# platine.net
KiCad netlist of a schematic drawn in EAGLE
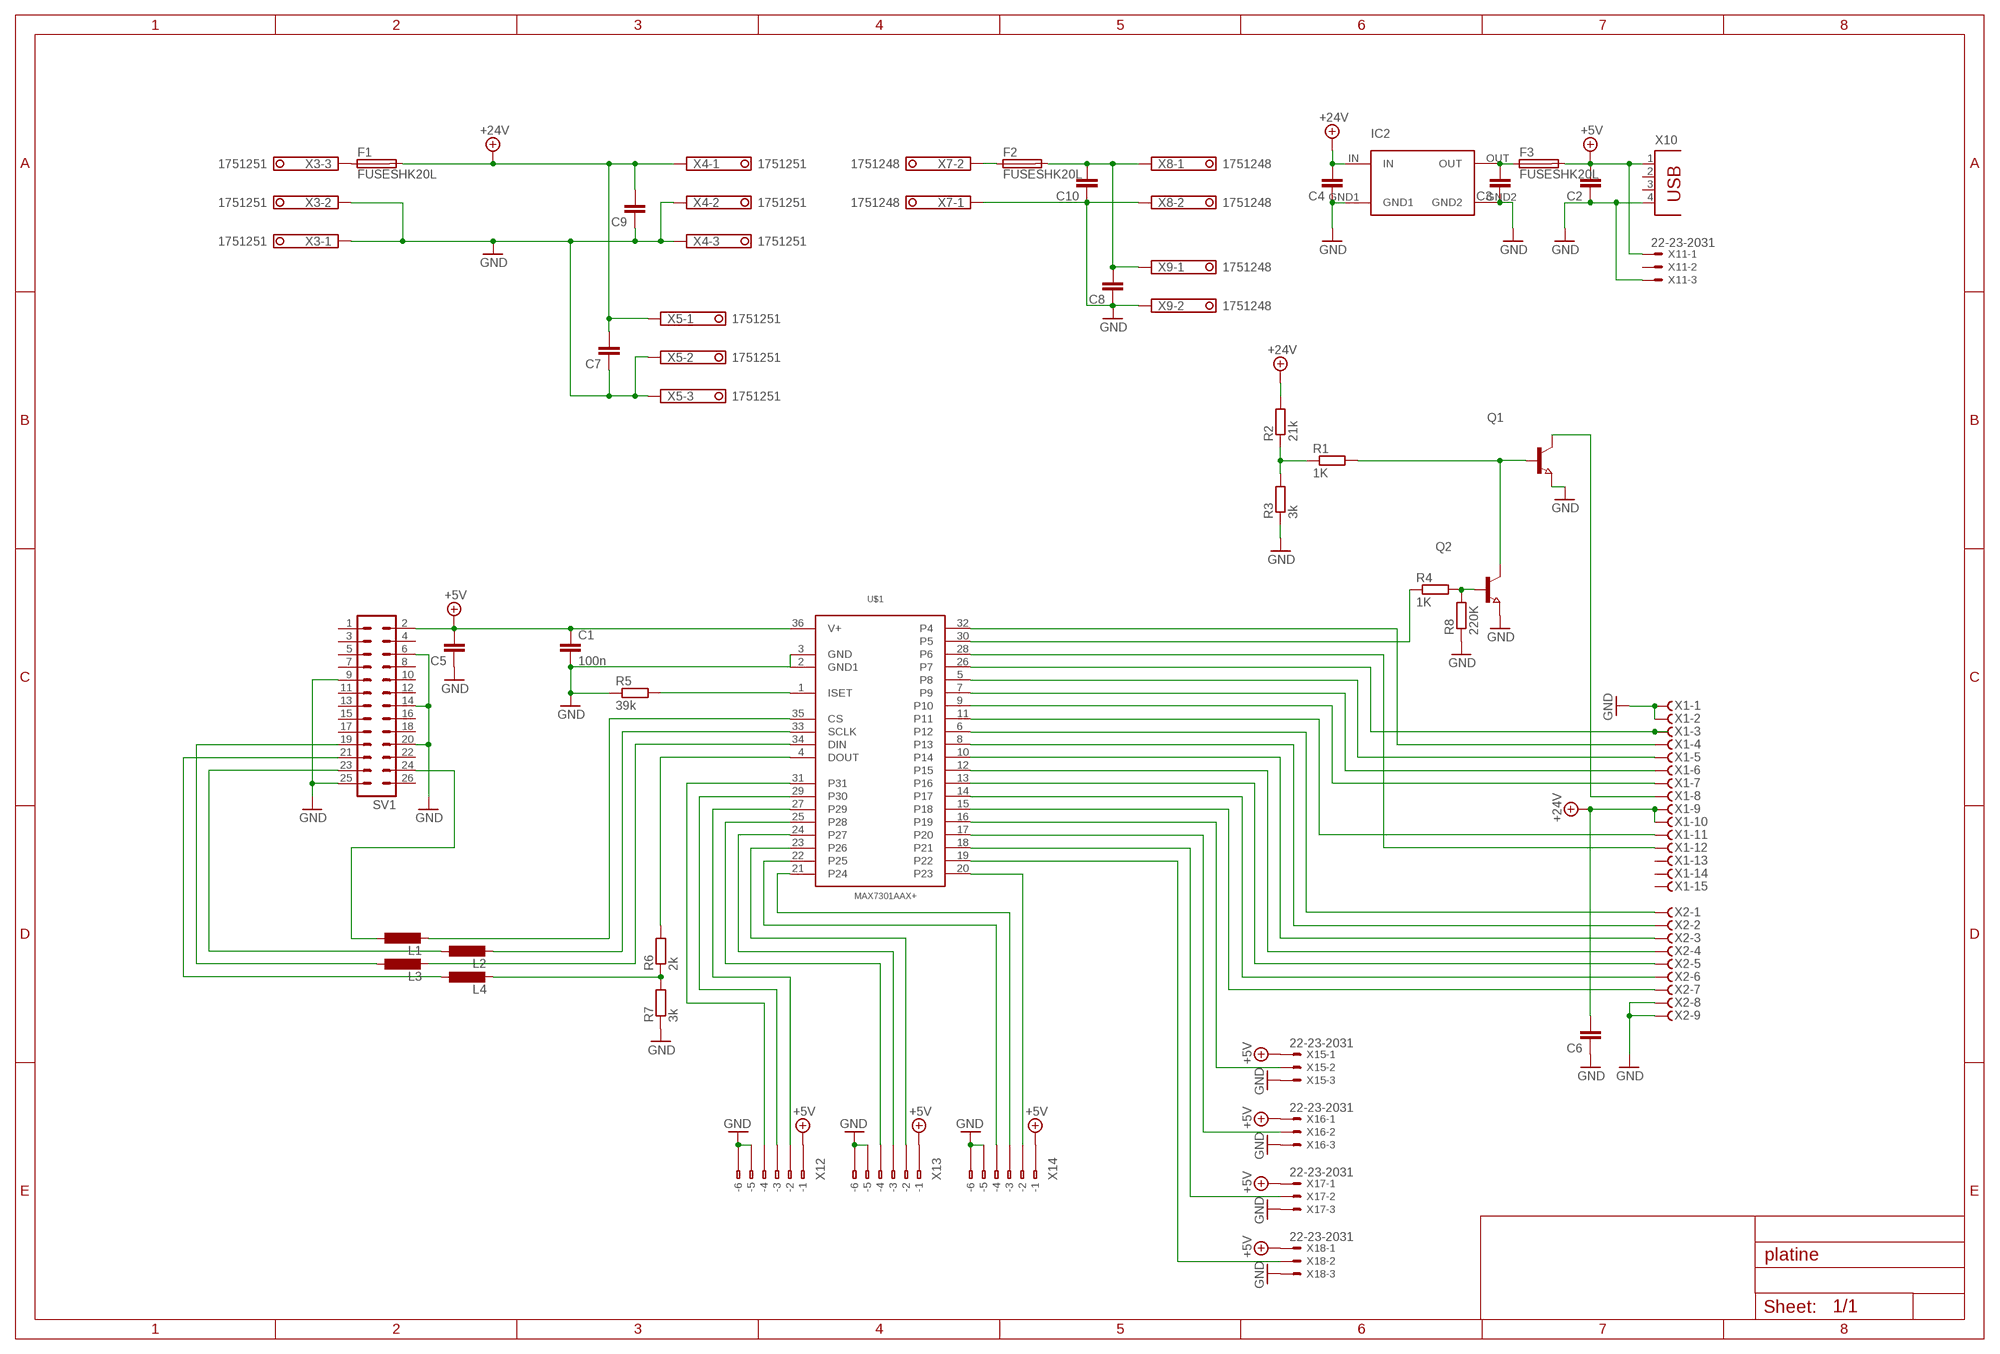
[diagram p0: schematic, sheet 1]

(export (version "E")
  (design (tool "Eeschema 10.0.6"))
  (components
    (comp (ref "C1")
      (value "100n")
      (footprint "eagle-import:C0603")
      (libsource (lib "eagle-import") (part "C-EUC0603"))
    )
    (comp (ref "C2")
      (value "C-EUC1206")
      (footprint "eagle-import:C1206")
      (libsource (lib "eagle-import") (part "C-EUC1206"))
    )
    (comp (ref "C3")
      (value "C-EUC1206")
      (footprint "eagle-import:C1206")
      (libsource (lib "eagle-import") (part "C-EUC1206"))
    )
    (comp (ref "C4")
      (value "C-EUC1206")
      (footprint "eagle-import:C1206")
      (libsource (lib "eagle-import") (part "C-EUC1206"))
    )
    (comp (ref "C5")
      (value "C-EUC1206")
      (footprint "eagle-import:C1206")
      (libsource (lib "eagle-import") (part "C-EUC1206"))
    )
    (comp (ref "C6")
      (value "C-EUC1206")
      (footprint "eagle-import:C1206")
      (libsource (lib "eagle-import") (part "C-EUC1206"))
    )
    (comp (ref "C7")
      (value "C-EUC1206")
      (footprint "eagle-import:C1206")
      (libsource (lib "eagle-import") (part "C-EUC1206"))
    )
    (comp (ref "C8")
      (value "C-EUC1206")
      (footprint "eagle-import:C1206")
      (libsource (lib "eagle-import") (part "C-EUC1206"))
    )
    (comp (ref "C9")
      (value "C-EUC1206")
      (footprint "eagle-import:C1206")
      (libsource (lib "eagle-import") (part "C-EUC1206"))
    )
    (comp (ref "C10")
      (value "C-EUC1206")
      (footprint "eagle-import:C1206")
      (libsource (lib "eagle-import") (part "C-EUC1206"))
    )
    (comp (ref "F1")
      (value "FUSESHK20L")
      (footprint "eagle-import:SHK20L")
      (libsource (lib "eagle-import") (part "FUSESHK20L"))
    )
    (comp (ref "F2")
      (value "FUSESHK20L")
      (footprint "eagle-import:SHK20L")
      (libsource (lib "eagle-import") (part "FUSESHK20L"))
    )
    (comp (ref "F3")
      (value "FUSESHK20L")
      (footprint "eagle-import:SHK20L")
      (libsource (lib "eagle-import") (part "FUSESHK20L"))
    )
    (comp (ref "IC2")
      (value "SPS-1")
      (footprint "eagle-import:SPS-1")
      (libsource (lib "eagle-import") (part "SPS-1"))
    )
    (comp (ref "L1")
      (value "L-EUL0402")
      (footprint "eagle-import:R0402")
      (libsource (lib "eagle-import") (part "L-EUL0402"))
    )
    (comp (ref "L2")
      (value "L-EUL0402")
      (footprint "eagle-import:R0402")
      (libsource (lib "eagle-import") (part "L-EUL0402"))
    )
    (comp (ref "L3")
      (value "L-EUL0402")
      (footprint "eagle-import:R0402")
      (libsource (lib "eagle-import") (part "L-EUL0402"))
    )
    (comp (ref "L4")
      (value "L-EUL0402")
      (footprint "eagle-import:R0402")
      (libsource (lib "eagle-import") (part "L-EUL0402"))
    )
    (comp (ref "Q1")
      (value "NPN-TRANSISTOR_SOT23")
      (footprint "eagle-import:SOT23")
      (libsource (lib "eagle-import") (part "NPN-TRANSISTOR_SOT23"))
    )
    (comp (ref "Q2")
      (value "NPN-TRANSISTOR_SOT23")
      (footprint "eagle-import:SOT23")
      (libsource (lib "eagle-import") (part "NPN-TRANSISTOR_SOT23"))
    )
    (comp (ref "R1")
      (value "1K")
      (footprint "eagle-import:R0603")
      (libsource (lib "eagle-import") (part "R-EU_R0603"))
    )
    (comp (ref "R2")
      (value "21k")
      (footprint "eagle-import:R0603")
      (libsource (lib "eagle-import") (part "R-EU_R0603"))
    )
    (comp (ref "R3")
      (value "3k")
      (footprint "eagle-import:R0603")
      (libsource (lib "eagle-import") (part "R-EU_R0603"))
    )
    (comp (ref "R4")
      (value "1K")
      (footprint "eagle-import:R0603")
      (libsource (lib "eagle-import") (part "R-EU_R0603"))
    )
    (comp (ref "R5")
      (value "39k")
      (footprint "eagle-import:R0603")
      (libsource (lib "eagle-import") (part "R-EU_R0603"))
    )
    (comp (ref "R6")
      (value "2k")
      (footprint "eagle-import:R0603")
      (libsource (lib "eagle-import") (part "R-EU_R0603"))
    )
    (comp (ref "R7")
      (value "3k")
      (footprint "eagle-import:R0603")
      (libsource (lib "eagle-import") (part "R-EU_R0603"))
    )
    (comp (ref "R8")
      (value "220K")
      (footprint "eagle-import:R0603")
      (libsource (lib "eagle-import") (part "R-EU_R0603"))
    )
    (comp (ref "SV1")
      (value "MA13-2")
      (footprint "eagle-import:MA13-2")
      (libsource (lib "eagle-import") (part "MA13-2"))
    )
    (comp (ref "U$1")
      (value "MAX7301AAX+")
      (footprint "eagle-import:SSOP36")
      (libsource (lib "eagle-import") (part "MAX7301AAX+"))
    )
    (comp (ref "X1")
      (value "F15HPS")
      (footprint "eagle-import:F15HP")
      (libsource (lib "eagle-import") (part "F15?SHP"))
    )
    (comp (ref "X2")
      (value "F09HPS")
      (footprint "eagle-import:F09HP")
      (libsource (lib "eagle-import") (part "F09?SHP"))
    )
    (comp (ref "X3")
      (value "1751251")
      (footprint "eagle-import:1751251")
      (libsource (lib "eagle-import") (part "1751251"))
    )
    (comp (ref "X4")
      (value "1751251")
      (footprint "eagle-import:1751251")
      (libsource (lib "eagle-import") (part "1751251"))
    )
    (comp (ref "X5")
      (value "1751251")
      (footprint "eagle-import:1751251")
      (libsource (lib "eagle-import") (part "1751251"))
    )
    (comp (ref "X7")
      (value "1751248")
      (footprint "eagle-import:1751248")
      (libsource (lib "eagle-import") (part "1751248"))
    )
    (comp (ref "X8")
      (value "1751248")
      (footprint "eagle-import:1751248")
      (libsource (lib "eagle-import") (part "1751248"))
    )
    (comp (ref "X9")
      (value "1751248")
      (footprint "eagle-import:1751248")
      (libsource (lib "eagle-import") (part "1751248"))
    )
    (comp (ref "X10")
      (value "PN87520")
      (footprint "eagle-import:PN87520")
      (libsource (lib "eagle-import") (part "PN87520"))
    )
    (comp (ref "X11")
      (value "22-23-2031")
      (footprint "eagle-import:22-23-2031")
      (fields (field (name "MF") "MOLEX"))
      (libsource (lib "eagle-import") (part "22-23-2031"))
    )
    (comp (ref "X12")
      (value "233-506")
      (footprint "eagle-import:233-506")
      (fields (field (name "MF") "Wago Corporation") (field (name "MPN") "0233-0506"))
      (libsource (lib "eagle-import") (part "233-506"))
    )
    (comp (ref "X13")
      (value "233-506")
      (footprint "eagle-import:233-506")
      (fields (field (name "MF") "Wago Corporation") (field (name "MPN") "0233-0506"))
      (libsource (lib "eagle-import") (part "233-506"))
    )
    (comp (ref "X14")
      (value "233-506")
      (footprint "eagle-import:233-506")
      (fields (field (name "MF") "Wago Corporation") (field (name "MPN") "0233-0506"))
      (libsource (lib "eagle-import") (part "233-506"))
    )
    (comp (ref "X15")
      (value "22-23-2031")
      (footprint "eagle-import:22-23-2031")
      (fields (field (name "MF") "MOLEX"))
      (libsource (lib "eagle-import") (part "22-23-2031"))
    )
    (comp (ref "X16")
      (value "22-23-2031")
      (footprint "eagle-import:22-23-2031")
      (fields (field (name "MF") "MOLEX"))
      (libsource (lib "eagle-import") (part "22-23-2031"))
    )
    (comp (ref "X17")
      (value "22-23-2031")
      (footprint "eagle-import:22-23-2031")
      (fields (field (name "MF") "MOLEX"))
      (libsource (lib "eagle-import") (part "22-23-2031"))
    )
    (comp (ref "X18")
      (value "22-23-2031")
      (footprint "eagle-import:22-23-2031")
      (fields (field (name "MF") "MOLEX"))
      (libsource (lib "eagle-import") (part "22-23-2031"))
    )
  )
  (nets
    (net (code "1") (name "+5V") (class "Default")
      (node (ref "C1") (pin "1") (pinfunction "1_1") (pintype "passive"))
      (node (ref "C2") (pin "2") (pinfunction "2_2") (pintype "passive"))
      (node (ref "C5") (pin "2") (pinfunction "2_2") (pintype "passive"))
      (node (ref "F3") (pin "2A") (pinfunction "2_2A") (pintype "passive"))
      (node (ref "SV1") (pin "2") (pinfunction "2_2") (pintype "passive"))
      (node (ref "U$1") (pin "36") (pinfunction "V+_36") (pintype "power_in"))
      (node (ref "X10") (pin "1") (pinfunction "1_1") (pintype "passive"))
      (node (ref "X11") (pin "1") (pinfunction "S_1") (pintype "passive"))
      (node (ref "X12") (pin "B1") (pinfunction "B-1_B1") (pintype "passive"))
      (node (ref "X13") (pin "B1") (pinfunction "B-1_B1") (pintype "passive"))
      (node (ref "X14") (pin "B1") (pinfunction "B-1_B1") (pintype "passive"))
      (node (ref "X15") (pin "1") (pinfunction "S_1") (pintype "passive"))
      (node (ref "X16") (pin "1") (pinfunction "S_1") (pintype "passive"))
      (node (ref "X17") (pin "1") (pinfunction "S_1") (pintype "passive"))
      (node (ref "X18") (pin "1") (pinfunction "S_1") (pintype "passive"))
    )
    (net (code "2") (name "+24V") (class "Default")
      (node (ref "C4") (pin "2") (pinfunction "2_2") (pintype "passive"))
      (node (ref "C6") (pin "2") (pinfunction "2_2") (pintype "passive"))
      (node (ref "C7") (pin "2") (pinfunction "2_2") (pintype "passive"))
      (node (ref "C9") (pin "2") (pinfunction "2_2") (pintype "passive"))
      (node (ref "F1") (pin "2A") (pinfunction "2_2A") (pintype "passive"))
      (node (ref "IC2") (pin "IN") (pinfunction "IN_IN") (pintype "bidirectional"))
      (node (ref "R2") (pin "2") (pinfunction "2_2") (pintype "passive"))
      (node (ref "X1") (pin "10") (pinfunction "F_10") (pintype "passive"))
      (node (ref "X1") (pin "9") (pinfunction "F_9") (pintype "passive"))
      (node (ref "X4") (pin "1") (pinfunction "K_1") (pintype "passive"))
      (node (ref "X5") (pin "1") (pinfunction "K_1") (pintype "passive"))
    )
    (net (code "3") (name "GND") (class "Default")
      (node (ref "C1") (pin "2") (pinfunction "2_2") (pintype "passive"))
      (node (ref "C10") (pin "1") (pinfunction "1_1") (pintype "passive"))
      (node (ref "C2") (pin "1") (pinfunction "1_1") (pintype "passive"))
      (node (ref "C3") (pin "1") (pinfunction "1_1") (pintype "passive"))
      (node (ref "C4") (pin "1") (pinfunction "1_1") (pintype "passive"))
      (node (ref "C5") (pin "1") (pinfunction "1_1") (pintype "passive"))
      (node (ref "C6") (pin "1") (pinfunction "1_1") (pintype "passive"))
      (node (ref "C7") (pin "1") (pinfunction "1_1") (pintype "passive"))
      (node (ref "C8") (pin "1") (pinfunction "1_1") (pintype "passive"))
      (node (ref "C9") (pin "1") (pinfunction "1_1") (pintype "passive"))
      (node (ref "IC2") (pin "GND1") (pinfunction "GND1_GND1") (pintype "bidirectional"))
      (node (ref "IC2") (pin "GND2") (pinfunction "GND2_GND2") (pintype "bidirectional"))
      (node (ref "Q1") (pin "2") (pinfunction "E_2") (pintype "passive"))
      (node (ref "Q2") (pin "2") (pinfunction "E_2") (pintype "passive"))
      (node (ref "R3") (pin "1") (pinfunction "1_1") (pintype "passive"))
      (node (ref "R5") (pin "1") (pinfunction "1_1") (pintype "passive"))
      (node (ref "R7") (pin "1") (pinfunction "1_1") (pintype "passive"))
      (node (ref "R8") (pin "1") (pinfunction "1_1") (pintype "passive"))
      (node (ref "SV1") (pin "14") (pinfunction "14_14") (pintype "passive"))
      (node (ref "SV1") (pin "20") (pinfunction "20_20") (pintype "passive"))
      (node (ref "SV1") (pin "25") (pinfunction "25_25") (pintype "passive"))
      (node (ref "SV1") (pin "6") (pinfunction "6_6") (pintype "passive"))
      (node (ref "SV1") (pin "9") (pinfunction "9_9") (pintype "passive"))
      (node (ref "U$1") (pin "2") (pinfunction "GND1_2") (pintype "power_in"))
      (node (ref "U$1") (pin "3") (pinfunction "GND_3") (pintype "power_in"))
      (node (ref "X1") (pin "1") (pinfunction "F_1") (pintype "passive"))
      (node (ref "X1") (pin "2") (pinfunction "F_2") (pintype "passive"))
      (node (ref "X10") (pin "4") (pinfunction "4_4") (pintype "passive"))
      (node (ref "X11") (pin "3") (pinfunction "S_3") (pintype "passive"))
      (node (ref "X12") (pin "B5") (pinfunction "B-5_B5") (pintype "passive"))
      (node (ref "X12") (pin "B6") (pinfunction "B-6_B6") (pintype "passive"))
      (node (ref "X13") (pin "B5") (pinfunction "B-5_B5") (pintype "passive"))
      (node (ref "X13") (pin "B6") (pinfunction "B-6_B6") (pintype "passive"))
      (node (ref "X14") (pin "B5") (pinfunction "B-5_B5") (pintype "passive"))
      (node (ref "X14") (pin "B6") (pinfunction "B-6_B6") (pintype "passive"))
      (node (ref "X15") (pin "3") (pinfunction "S_3") (pintype "passive"))
      (node (ref "X16") (pin "3") (pinfunction "S_3") (pintype "passive"))
      (node (ref "X17") (pin "3") (pinfunction "S_3") (pintype "passive"))
      (node (ref "X18") (pin "3") (pinfunction "S_3") (pintype "passive"))
      (node (ref "X2") (pin "8") (pinfunction "F_8") (pintype "passive"))
      (node (ref "X2") (pin "9") (pinfunction "F_9") (pintype "passive"))
      (node (ref "X3") (pin "1") (pinfunction "K_1") (pintype "passive"))
      (node (ref "X3") (pin "2") (pinfunction "K_2") (pintype "passive"))
      (node (ref "X4") (pin "2") (pinfunction "K_2") (pintype "passive"))
      (node (ref "X4") (pin "3") (pinfunction "K_3") (pintype "passive"))
      (node (ref "X5") (pin "2") (pinfunction "K_2") (pintype "passive"))
      (node (ref "X5") (pin "3") (pinfunction "K_3") (pintype "passive"))
      (node (ref "X7") (pin "1") (pinfunction "K_1") (pintype "passive"))
      (node (ref "X8") (pin "2") (pinfunction "K_2") (pintype "passive"))
      (node (ref "X9") (pin "2") (pinfunction "K_2") (pintype "passive"))
    )
    (net (code "4") (name "Net-(F1-1)") (class "Default")
      (node (ref "F1") (pin "1A") (pinfunction "1_1A") (pintype "passive"))
      (node (ref "X3") (pin "3") (pinfunction "K_3") (pintype "passive"))
    )
    (net (code "5") (name "Net-(F2-1)") (class "Default")
      (node (ref "F2") (pin "1A") (pinfunction "1_1A") (pintype "passive"))
      (node (ref "X7") (pin "2") (pinfunction "K_2") (pintype "passive"))
    )
    (net (code "6") (name "Net-(F2-2)") (class "Default")
      (node (ref "C10") (pin "2") (pinfunction "2_2") (pintype "passive"))
      (node (ref "C8") (pin "2") (pinfunction "2_2") (pintype "passive"))
      (node (ref "F2") (pin "2A") (pinfunction "2_2A") (pintype "passive"))
      (node (ref "X8") (pin "1") (pinfunction "K_1") (pintype "passive"))
      (node (ref "X9") (pin "1") (pinfunction "K_1") (pintype "passive"))
    )
    (net (code "7") (name "Net-(F3-1)") (class "Default")
      (node (ref "C3") (pin "2") (pinfunction "2_2") (pintype "passive"))
      (node (ref "F3") (pin "1A") (pinfunction "1_1A") (pintype "passive"))
      (node (ref "IC2") (pin "OUT") (pinfunction "OUT_OUT") (pintype "bidirectional"))
    )
    (net (code "8") (name "Net-(L1-Pad1)") (class "Default")
      (node (ref "L1") (pin "1") (pinfunction "1_1") (pintype "passive"))
      (node (ref "SV1") (pin "24") (pinfunction "24_24") (pintype "passive"))
    )
    (net (code "9") (name "Net-(L2-Pad1)") (class "Default")
      (node (ref "L2") (pin "1") (pinfunction "1_1") (pintype "passive"))
      (node (ref "SV1") (pin "23") (pinfunction "23_23") (pintype "passive"))
    )
    (net (code "10") (name "Net-(L3-Pad1)") (class "Default")
      (node (ref "L3") (pin "1") (pinfunction "1_1") (pintype "passive"))
      (node (ref "SV1") (pin "19") (pinfunction "19_19") (pintype "passive"))
    )
    (net (code "11") (name "Net-(L4-Pad1)") (class "Default")
      (node (ref "L4") (pin "1") (pinfunction "1_1") (pintype "passive"))
      (node (ref "SV1") (pin "21") (pinfunction "21_21") (pintype "passive"))
    )
    (net (code "12") (name "Net-(L4-Pad2)") (class "Default")
      (node (ref "L4") (pin "2") (pinfunction "2_2") (pintype "passive"))
      (node (ref "R6") (pin "1") (pinfunction "1_1") (pintype "passive"))
      (node (ref "R7") (pin "2") (pinfunction "2_2") (pintype "passive"))
    )
    (net (code "13") (name "Net-(Q1-B)") (class "Default")
      (node (ref "Q1") (pin "1") (pinfunction "B_1") (pintype "passive"))
      (node (ref "Q2") (pin "3") (pinfunction "C_3") (pintype "passive"))
      (node (ref "R1") (pin "2") (pinfunction "2_2") (pintype "passive"))
    )
    (net (code "14") (name "Net-(Q1-C)") (class "Default")
      (node (ref "Q1") (pin "3") (pinfunction "C_3") (pintype "passive"))
      (node (ref "X1") (pin "8") (pinfunction "F_8") (pintype "passive"))
    )
    (net (code "15") (name "Net-(Q2-B)") (class "Default")
      (node (ref "Q2") (pin "1") (pinfunction "B_1") (pintype "passive"))
      (node (ref "R4") (pin "2") (pinfunction "2_2") (pintype "passive"))
      (node (ref "R8") (pin "2") (pinfunction "2_2") (pintype "passive"))
    )
    (net (code "16") (name "Net-(R1-Pad1)") (class "Default")
      (node (ref "R1") (pin "1") (pinfunction "1_1") (pintype "passive"))
      (node (ref "R2") (pin "1") (pinfunction "1_1") (pintype "passive"))
      (node (ref "R3") (pin "2") (pinfunction "2_2") (pintype "passive"))
    )
    (net (code "17") (name "Net-(U$1-CS)") (class "Default")
      (node (ref "L1") (pin "2") (pinfunction "2_2") (pintype "passive"))
      (node (ref "U$1") (pin "35") (pinfunction "CS_35") (pintype "bidirectional"))
    )
    (net (code "18") (name "Net-(U$1-DIN)") (class "Default")
      (node (ref "L3") (pin "2") (pinfunction "2_2") (pintype "passive"))
      (node (ref "U$1") (pin "34") (pinfunction "DIN_34") (pintype "bidirectional"))
    )
    (net (code "19") (name "Net-(U$1-DOUT)") (class "Default")
      (node (ref "R6") (pin "2") (pinfunction "2_2") (pintype "passive"))
      (node (ref "U$1") (pin "4") (pinfunction "DOUT_4") (pintype "bidirectional"))
    )
    (net (code "20") (name "Net-(U$1-ISET)") (class "Default")
      (node (ref "R5") (pin "2") (pinfunction "2_2") (pintype "passive"))
      (node (ref "U$1") (pin "1") (pinfunction "ISET_1") (pintype "bidirectional"))
    )
    (net (code "21") (name "Net-(U$1-P4)") (class "Default")
      (node (ref "U$1") (pin "32") (pinfunction "P4_32") (pintype "bidirectional"))
      (node (ref "X1") (pin "4") (pinfunction "F_4") (pintype "passive"))
    )
    (net (code "22") (name "Net-(U$1-P5)") (class "Default")
      (node (ref "R4") (pin "1") (pinfunction "1_1") (pintype "passive"))
      (node (ref "U$1") (pin "30") (pinfunction "P5_30") (pintype "bidirectional"))
    )
    (net (code "23") (name "Net-(U$1-P6)") (class "Default")
      (node (ref "U$1") (pin "28") (pinfunction "P6_28") (pintype "bidirectional"))
      (node (ref "X1") (pin "12") (pinfunction "F_12") (pintype "passive"))
    )
    (net (code "24") (name "Net-(U$1-P7)") (class "Default")
      (node (ref "U$1") (pin "26") (pinfunction "P7_26") (pintype "bidirectional"))
      (node (ref "X1") (pin "3") (pinfunction "F_3") (pintype "passive"))
    )
    (net (code "25") (name "Net-(U$1-P8)") (class "Default")
      (node (ref "U$1") (pin "5") (pinfunction "P8_5") (pintype "bidirectional"))
      (node (ref "X1") (pin "5") (pinfunction "F_5") (pintype "passive"))
    )
    (net (code "26") (name "Net-(U$1-P9)") (class "Default")
      (node (ref "U$1") (pin "7") (pinfunction "P9_7") (pintype "bidirectional"))
      (node (ref "X1") (pin "6") (pinfunction "F_6") (pintype "passive"))
    )
    (net (code "27") (name "Net-(U$1-P10)") (class "Default")
      (node (ref "U$1") (pin "9") (pinfunction "P10_9") (pintype "bidirectional"))
      (node (ref "X1") (pin "7") (pinfunction "F_7") (pintype "passive"))
    )
    (net (code "28") (name "Net-(U$1-P11)") (class "Default")
      (node (ref "U$1") (pin "11") (pinfunction "P11_11") (pintype "bidirectional"))
      (node (ref "X1") (pin "11") (pinfunction "F_11") (pintype "passive"))
    )
    (net (code "29") (name "Net-(U$1-P12)") (class "Default")
      (node (ref "U$1") (pin "6") (pinfunction "P12_6") (pintype "bidirectional"))
      (node (ref "X2") (pin "1") (pinfunction "F_1") (pintype "passive"))
    )
    (net (code "30") (name "Net-(U$1-P13)") (class "Default")
      (node (ref "U$1") (pin "8") (pinfunction "P13_8") (pintype "bidirectional"))
      (node (ref "X2") (pin "2") (pinfunction "F_2") (pintype "passive"))
    )
    (net (code "31") (name "Net-(U$1-P14)") (class "Default")
      (node (ref "U$1") (pin "10") (pinfunction "P14_10") (pintype "bidirectional"))
      (node (ref "X2") (pin "3") (pinfunction "F_3") (pintype "passive"))
    )
    (net (code "32") (name "Net-(U$1-P15)") (class "Default")
      (node (ref "U$1") (pin "12") (pinfunction "P15_12") (pintype "bidirectional"))
      (node (ref "X2") (pin "4") (pinfunction "F_4") (pintype "passive"))
    )
    (net (code "33") (name "Net-(U$1-P16)") (class "Default")
      (node (ref "U$1") (pin "13") (pinfunction "P16_13") (pintype "bidirectional"))
      (node (ref "X2") (pin "5") (pinfunction "F_5") (pintype "passive"))
    )
    (net (code "34") (name "Net-(U$1-P17)") (class "Default")
      (node (ref "U$1") (pin "14") (pinfunction "P17_14") (pintype "bidirectional"))
      (node (ref "X2") (pin "6") (pinfunction "F_6") (pintype "passive"))
    )
    (net (code "35") (name "Net-(U$1-P18)") (class "Default")
      (node (ref "U$1") (pin "15") (pinfunction "P18_15") (pintype "bidirectional"))
      (node (ref "X2") (pin "7") (pinfunction "F_7") (pintype "passive"))
    )
    (net (code "36") (name "Net-(U$1-P19)") (class "Default")
      (node (ref "U$1") (pin "16") (pinfunction "P19_16") (pintype "bidirectional"))
      (node (ref "X15") (pin "2") (pinfunction "S_2") (pintype "passive"))
    )
    (net (code "37") (name "Net-(U$1-P20)") (class "Default")
      (node (ref "U$1") (pin "17") (pinfunction "P20_17") (pintype "bidirectional"))
      (node (ref "X16") (pin "2") (pinfunction "S_2") (pintype "passive"))
    )
    (net (code "38") (name "Net-(U$1-P21)") (class "Default")
      (node (ref "U$1") (pin "18") (pinfunction "P21_18") (pintype "bidirectional"))
      (node (ref "X17") (pin "2") (pinfunction "S_2") (pintype "passive"))
    )
    (net (code "39") (name "Net-(U$1-P22)") (class "Default")
      (node (ref "U$1") (pin "19") (pinfunction "P22_19") (pintype "bidirectional"))
      (node (ref "X18") (pin "2") (pinfunction "S_2") (pintype "passive"))
    )
    (net (code "40") (name "Net-(U$1-P23)") (class "Default")
      (node (ref "U$1") (pin "20") (pinfunction "P23_20") (pintype "bidirectional"))
      (node (ref "X14") (pin "B2") (pinfunction "B-2_B2") (pintype "passive"))
    )
    (net (code "41") (name "Net-(U$1-P24)") (class "Default")
      (node (ref "U$1") (pin "21") (pinfunction "P24_21") (pintype "bidirectional"))
      (node (ref "X14") (pin "B3") (pinfunction "B-3_B3") (pintype "passive"))
    )
    (net (code "42") (name "Net-(U$1-P25)") (class "Default")
      (node (ref "U$1") (pin "22") (pinfunction "P25_22") (pintype "bidirectional"))
      (node (ref "X14") (pin "B4") (pinfunction "B-4_B4") (pintype "passive"))
    )
    (net (code "43") (name "Net-(U$1-P26)") (class "Default")
      (node (ref "U$1") (pin "23") (pinfunction "P26_23") (pintype "bidirectional"))
      (node (ref "X13") (pin "B2") (pinfunction "B-2_B2") (pintype "passive"))
    )
    (net (code "44") (name "Net-(U$1-P27)") (class "Default")
      (node (ref "U$1") (pin "24") (pinfunction "P27_24") (pintype "bidirectional"))
      (node (ref "X13") (pin "B3") (pinfunction "B-3_B3") (pintype "passive"))
    )
    (net (code "45") (name "Net-(U$1-P28)") (class "Default")
      (node (ref "U$1") (pin "25") (pinfunction "P28_25") (pintype "bidirectional"))
      (node (ref "X13") (pin "B4") (pinfunction "B-4_B4") (pintype "passive"))
    )
    (net (code "46") (name "Net-(U$1-P29)") (class "Default")
      (node (ref "U$1") (pin "27") (pinfunction "P29_27") (pintype "bidirectional"))
      (node (ref "X12") (pin "B2") (pinfunction "B-2_B2") (pintype "passive"))
    )
    (net (code "47") (name "Net-(U$1-P30)") (class "Default")
      (node (ref "U$1") (pin "29") (pinfunction "P30_29") (pintype "bidirectional"))
      (node (ref "X12") (pin "B3") (pinfunction "B-3_B3") (pintype "passive"))
    )
    (net (code "48") (name "Net-(U$1-P31)") (class "Default")
      (node (ref "U$1") (pin "31") (pinfunction "P31_31") (pintype "bidirectional"))
      (node (ref "X12") (pin "B4") (pinfunction "B-4_B4") (pintype "passive"))
    )
    (net (code "49") (name "Net-(U$1-SCLK)") (class "Default")
      (node (ref "L2") (pin "2") (pinfunction "2_2") (pintype "passive"))
      (node (ref "U$1") (pin "33") (pinfunction "SCLK_33") (pintype "bidirectional"))
    )
    (net (code "50") (name "unconnected-(SV1-Pad1)") (class "Default")
      (node (ref "SV1") (pin "1") (pinfunction "1_1") (pintype "passive"))
    )
    (net (code "51") (name "unconnected-(SV1-Pad3)") (class "Default")
      (node (ref "SV1") (pin "3") (pinfunction "3_3") (pintype "passive"))
    )
    (net (code "52") (name "unconnected-(SV1-Pad4)") (class "Default")
      (node (ref "SV1") (pin "4") (pinfunction "4_4") (pintype "passive"))
    )
    (net (code "53") (name "unconnected-(SV1-Pad5)") (class "Default")
      (node (ref "SV1") (pin "5") (pinfunction "5_5") (pintype "passive"))
    )
    (net (code "54") (name "unconnected-(SV1-Pad7)") (class "Default")
      (node (ref "SV1") (pin "7") (pinfunction "7_7") (pintype "passive"))
    )
    (net (code "55") (name "unconnected-(SV1-Pad8)") (class "Default")
      (node (ref "SV1") (pin "8") (pinfunction "8_8") (pintype "passive"))
    )
    (net (code "56") (name "unconnected-(SV1-Pad10)") (class "Default")
      (node (ref "SV1") (pin "10") (pinfunction "10_10") (pintype "passive"))
    )
    (net (code "57") (name "unconnected-(SV1-Pad11)") (class "Default")
      (node (ref "SV1") (pin "11") (pinfunction "11_11") (pintype "passive"))
    )
    (net (code "58") (name "unconnected-(SV1-Pad12)") (class "Default")
      (node (ref "SV1") (pin "12") (pinfunction "12_12") (pintype "passive"))
    )
    (net (code "59") (name "unconnected-(SV1-Pad13)") (class "Default")
      (node (ref "SV1") (pin "13") (pinfunction "13_13") (pintype "passive"))
    )
    (net (code "60") (name "unconnected-(SV1-Pad15)") (class "Default")
      (node (ref "SV1") (pin "15") (pinfunction "15_15") (pintype "passive"))
    )
    (net (code "61") (name "unconnected-(SV1-Pad16)") (class "Default")
      (node (ref "SV1") (pin "16") (pinfunction "16_16") (pintype "passive"))
    )
    (net (code "62") (name "unconnected-(SV1-Pad17)") (class "Default")
      (node (ref "SV1") (pin "17") (pinfunction "17_17") (pintype "passive"))
    )
    (net (code "63") (name "unconnected-(SV1-Pad18)") (class "Default")
      (node (ref "SV1") (pin "18") (pinfunction "18_18") (pintype "passive"))
    )
    (net (code "64") (name "unconnected-(SV1-Pad22)") (class "Default")
      (node (ref "SV1") (pin "22") (pinfunction "22_22") (pintype "passive"))
    )
    (net (code "65") (name "unconnected-(SV1-Pad26)") (class "Default")
      (node (ref "SV1") (pin "26") (pinfunction "26_26") (pintype "passive"))
    )
    (net (code "66") (name "unconnected-(X1E-F-Pad13)") (class "Default")
      (node (ref "X1") (pin "13") (pinfunction "F_13") (pintype "passive"))
    )
    (net (code "67") (name "unconnected-(X1F-F-Pad14)") (class "Default")
      (node (ref "X1") (pin "14") (pinfunction "F_14") (pintype "passive"))
    )
    (net (code "68") (name "unconnected-(X1G-F-Pad15)") (class "Default")
      (node (ref "X1") (pin "15") (pinfunction "F_15") (pintype "passive"))
    )
    (net (code "69") (name "unconnected-(X10-Pad2)") (class "Default")
      (node (ref "X10") (pin "2") (pinfunction "2_2") (pintype "passive"))
    )
    (net (code "70") (name "unconnected-(X10-Pad3)") (class "Default")
      (node (ref "X10") (pin "3") (pinfunction "3_3") (pintype "passive"))
    )
    (net (code "71") (name "unconnected-(X11B-S-Pad2)") (class "Default")
      (node (ref "X11") (pin "2") (pinfunction "S_2") (pintype "passive"))
    )
    (net (code "72") (name "unconnected-(X12--1-PadA1)") (class "Default")
      (node (ref "X12") (pin "A1") (pinfunction "-1_A1") (pintype "passive"))
    )
    (net (code "73") (name "unconnected-(X12--2-PadA2)") (class "Default")
      (node (ref "X12") (pin "A2") (pinfunction "-2_A2") (pintype "passive"))
    )
    (net (code "74") (name "unconnected-(X12--3-PadA3)") (class "Default")
      (node (ref "X12") (pin "A3") (pinfunction "-3_A3") (pintype "passive"))
    )
    (net (code "75") (name "unconnected-(X12--4-PadA4)") (class "Default")
      (node (ref "X12") (pin "A4") (pinfunction "-4_A4") (pintype "passive"))
    )
    (net (code "76") (name "unconnected-(X12--5-PadA5)") (class "Default")
      (node (ref "X12") (pin "A5") (pinfunction "-5_A5") (pintype "passive"))
    )
    (net (code "77") (name "unconnected-(X12--6-PadA6)") (class "Default")
      (node (ref "X12") (pin "A6") (pinfunction "-6_A6") (pintype "passive"))
    )
    (net (code "78") (name "unconnected-(X13--1-PadA1)") (class "Default")
      (node (ref "X13") (pin "A1") (pinfunction "-1_A1") (pintype "passive"))
    )
    (net (code "79") (name "unconnected-(X13--2-PadA2)") (class "Default")
      (node (ref "X13") (pin "A2") (pinfunction "-2_A2") (pintype "passive"))
    )
    (net (code "80") (name "unconnected-(X13--3-PadA3)") (class "Default")
      (node (ref "X13") (pin "A3") (pinfunction "-3_A3") (pintype "passive"))
    )
    (net (code "81") (name "unconnected-(X13--4-PadA4)") (class "Default")
      (node (ref "X13") (pin "A4") (pinfunction "-4_A4") (pintype "passive"))
    )
    (net (code "82") (name "unconnected-(X13--5-PadA5)") (class "Default")
      (node (ref "X13") (pin "A5") (pinfunction "-5_A5") (pintype "passive"))
    )
    (net (code "83") (name "unconnected-(X13--6-PadA6)") (class "Default")
      (node (ref "X13") (pin "A6") (pinfunction "-6_A6") (pintype "passive"))
    )
    (net (code "84") (name "unconnected-(X14--1-PadA1)") (class "Default")
      (node (ref "X14") (pin "A1") (pinfunction "-1_A1") (pintype "passive"))
    )
    (net (code "85") (name "unconnected-(X14--2-PadA2)") (class "Default")
      (node (ref "X14") (pin "A2") (pinfunction "-2_A2") (pintype "passive"))
    )
    (net (code "86") (name "unconnected-(X14--3-PadA3)") (class "Default")
      (node (ref "X14") (pin "A3") (pinfunction "-3_A3") (pintype "passive"))
    )
    (net (code "87") (name "unconnected-(X14--4-PadA4)") (class "Default")
      (node (ref "X14") (pin "A4") (pinfunction "-4_A4") (pintype "passive"))
    )
    (net (code "88") (name "unconnected-(X14--5-PadA5)") (class "Default")
      (node (ref "X14") (pin "A5") (pinfunction "-5_A5") (pintype "passive"))
    )
    (net (code "89") (name "unconnected-(X14--6-PadA6)") (class "Default")
      (node (ref "X14") (pin "A6") (pinfunction "-6_A6") (pintype "passive"))
    )
  )
)
